# instruction-register.net
KiCad netlist of a schematic drawn in EAGLE
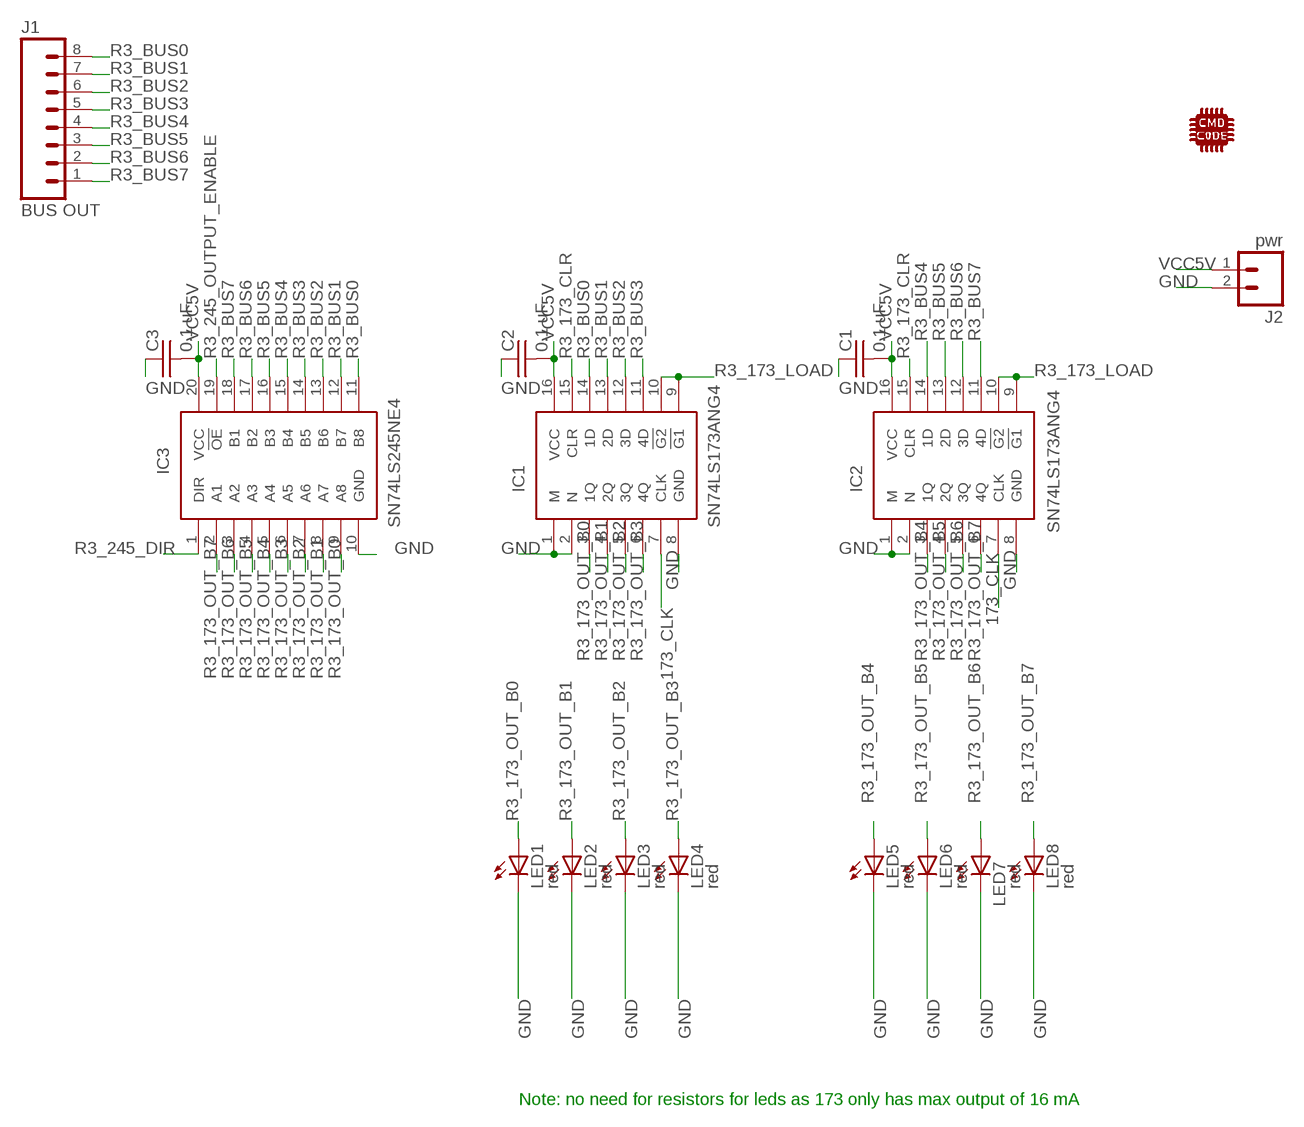
[diagram p0: schematic, sheet 1]
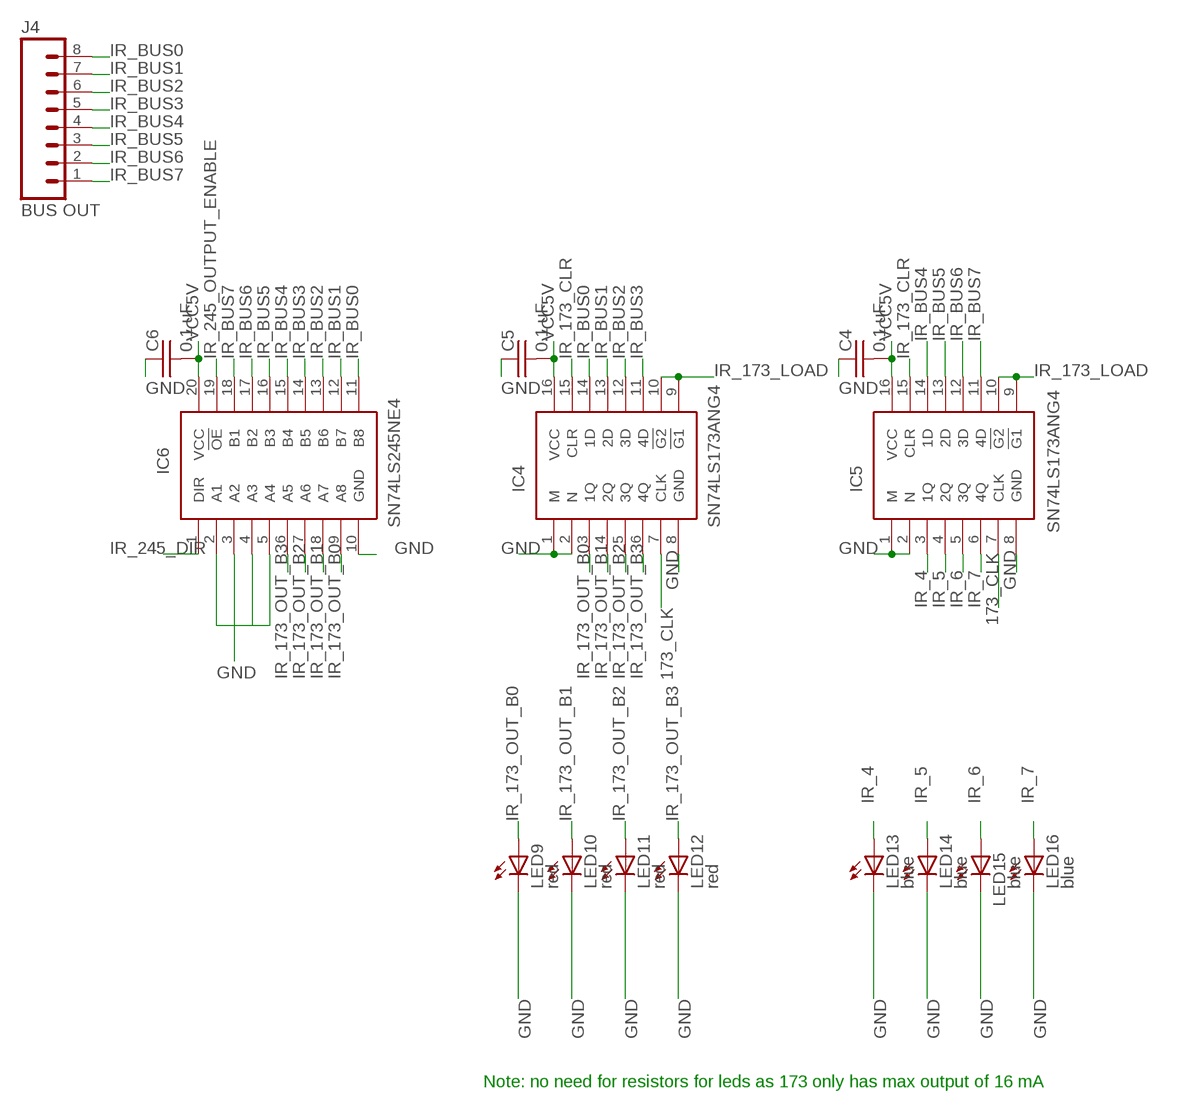
[diagram p1: schematic, sheet 2]
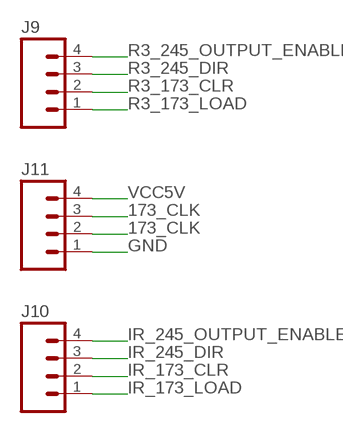
[diagram p2: schematic, sheet 3]

(export (version "E")
  (design (tool "Eeschema 10.0.6"))
  (components
    (comp (ref "C4")
      (value "0.1 uF")
      (footprint "eagle-import:C075-032X103")
      (libsource (lib "eagle-import") (part "C-US075-032X103"))
    )
    (comp (ref "C5")
      (value "0.1 uF")
      (footprint "eagle-import:C075-032X103")
      (libsource (lib "eagle-import") (part "C-US075-032X103"))
    )
    (comp (ref "C6")
      (value "0.1 uF")
      (footprint "eagle-import:C075-032X103")
      (libsource (lib "eagle-import") (part "C-US075-032X103"))
    )
    (comp (ref "IC4")
      (value "SN74LS173ANG4")
      (footprint "eagle-import:DIP794W53P254L1930H508Q16N")
      (libsource (lib "eagle-import") (part "SN74LS173ANG4"))
    )
    (comp (ref "IC5")
      (value "SN74LS173ANG4")
      (footprint "eagle-import:DIP794W53P254L1930H508Q16N")
      (libsource (lib "eagle-import") (part "SN74LS173ANG4"))
    )
    (comp (ref "IC6")
      (value "SN74LS245NE4")
      (footprint "eagle-import:DIP794W53P254L2540H508Q20N")
      (fields (field (name "MOUSER_PART_NUMBER") "595-SN74LS245NE4"))
      (libsource (lib "eagle-import") (part "SN74LS245NE4"))
    )
    (comp (ref "J4")
      (value "BUS OUT")
      (footprint "eagle-import:1X08_ROUND")
      (libsource (lib "eagle-import") (part "M08"))
    )
    (comp (ref "LED9")
      (value "red")
      (footprint "eagle-import:LED3MM")
      (libsource (lib "eagle-import") (part "LED3MM"))
    )
    (comp (ref "LED10")
      (value "red")
      (footprint "eagle-import:LED3MM")
      (libsource (lib "eagle-import") (part "LED3MM"))
    )
    (comp (ref "LED11")
      (value "red")
      (footprint "eagle-import:LED3MM")
      (libsource (lib "eagle-import") (part "LED3MM"))
    )
    (comp (ref "LED12")
      (value "red")
      (footprint "eagle-import:LED3MM")
      (libsource (lib "eagle-import") (part "LED3MM"))
    )
    (comp (ref "LED13")
      (value "blue")
      (footprint "eagle-import:LED3MM")
      (libsource (lib "eagle-import") (part "LED3MM"))
    )
    (comp (ref "LED14")
      (value "blue")
      (footprint "eagle-import:LED3MM")
      (libsource (lib "eagle-import") (part "LED3MM"))
    )
    (comp (ref "LED15")
      (value "blue")
      (footprint "eagle-import:LED3MM")
      (libsource (lib "eagle-import") (part "LED3MM"))
    )
    (comp (ref "LED16")
      (value "blue")
      (footprint "eagle-import:LED3MM")
      (libsource (lib "eagle-import") (part "LED3MM"))
    )
    (comp (ref "C1")
      (value "0.1 uF")
      (footprint "eagle-import:C075-032X103")
      (libsource (lib "eagle-import") (part "C-US075-032X103"))
    )
    (comp (ref "C2")
      (value "0.1 uF")
      (footprint "eagle-import:C075-032X103")
      (libsource (lib "eagle-import") (part "C-US075-032X103"))
    )
    (comp (ref "C3")
      (value "0.1 uF")
      (footprint "eagle-import:C075-032X103")
      (libsource (lib "eagle-import") (part "C-US075-032X103"))
    )
    (comp (ref "IC1")
      (value "SN74LS173ANG4")
      (footprint "eagle-import:DIP794W53P254L1930H508Q16N")
      (libsource (lib "eagle-import") (part "SN74LS173ANG4"))
    )
    (comp (ref "IC2")
      (value "SN74LS173ANG4")
      (footprint "eagle-import:DIP794W53P254L1930H508Q16N")
      (libsource (lib "eagle-import") (part "SN74LS173ANG4"))
    )
    (comp (ref "IC3")
      (value "SN74LS245NE4")
      (footprint "eagle-import:DIP794W53P254L2540H508Q20N")
      (fields (field (name "MOUSER_PART_NUMBER") "595-SN74LS245NE4"))
      (libsource (lib "eagle-import") (part "SN74LS245NE4"))
    )
    (comp (ref "J1")
      (value "BUS OUT")
      (footprint "eagle-import:1X08_ROUND")
      (libsource (lib "eagle-import") (part "M08"))
    )
    (comp (ref "J2")
      (value "pwr")
      (footprint "eagle-import:1X02")
      (libsource (lib "eagle-import") (part "M02PTH"))
    )
    (comp (ref "LED1")
      (value "red")
      (footprint "eagle-import:LED3MM")
      (libsource (lib "eagle-import") (part "LED3MM"))
    )
    (comp (ref "LED2")
      (value "red")
      (footprint "eagle-import:LED3MM")
      (libsource (lib "eagle-import") (part "LED3MM"))
    )
    (comp (ref "LED3")
      (value "red")
      (footprint "eagle-import:LED3MM")
      (libsource (lib "eagle-import") (part "LED3MM"))
    )
    (comp (ref "LED4")
      (value "red")
      (footprint "eagle-import:LED3MM")
      (libsource (lib "eagle-import") (part "LED3MM"))
    )
    (comp (ref "LED5")
      (value "red")
      (footprint "eagle-import:LED3MM")
      (libsource (lib "eagle-import") (part "LED3MM"))
    )
    (comp (ref "LED6")
      (value "red")
      (footprint "eagle-import:LED3MM")
      (libsource (lib "eagle-import") (part "LED3MM"))
    )
    (comp (ref "LED7")
      (value "red")
      (footprint "eagle-import:LED3MM")
      (libsource (lib "eagle-import") (part "LED3MM"))
    )
    (comp (ref "LED8")
      (value "red")
      (footprint "eagle-import:LED3MM")
      (libsource (lib "eagle-import") (part "LED3MM"))
    )
    (comp (ref "U$1")
      (value "CMD_C0DE_LOGOCMD_CODE_LOGO_TOP_COPPER")
      (footprint "eagle-import:CMD_C0DE_LOGO_TOP_COPPER")
      (libsource (lib "eagle-import") (part "CMD_C0DE_LOGOCMD_CODE_LOGO_TOP_COPPER"))
    )
    (comp (ref "J9")
      (value "M04PTH")
      (footprint "eagle-import:1X04")
      (libsource (lib "eagle-import") (part "M04PTH"))
    )
    (comp (ref "J10")
      (value "M04PTH")
      (footprint "eagle-import:1X04")
      (libsource (lib "eagle-import") (part "M04PTH"))
    )
    (comp (ref "J11")
      (value "M04PTH")
      (footprint "eagle-import:1X04")
      (libsource (lib "eagle-import") (part "M04PTH"))
    )
  )
  (nets
    (net (code "1") (name "173_CLK") (class "Default")
      (node (ref "IC1") (pin "7") (pinfunction "CLK_7") (pintype "bidirectional"))
      (node (ref "IC2") (pin "7") (pinfunction "CLK_7") (pintype "bidirectional"))
      (node (ref "IC4") (pin "7") (pinfunction "CLK_7") (pintype "bidirectional"))
      (node (ref "IC5") (pin "7") (pinfunction "CLK_7") (pintype "bidirectional"))
      (node (ref "J11") (pin "2") (pinfunction "2_2") (pintype "passive"))
      (node (ref "J11") (pin "3") (pinfunction "3_3") (pintype "passive"))
    )
    (net (code "2") (name "GND") (class "Default")
      (node (ref "C1") (pin "1") (pinfunction "1_1") (pintype "passive"))
      (node (ref "C2") (pin "1") (pinfunction "1_1") (pintype "passive"))
      (node (ref "C3") (pin "1") (pinfunction "1_1") (pintype "passive"))
      (node (ref "C4") (pin "1") (pinfunction "1_1") (pintype "passive"))
      (node (ref "C5") (pin "1") (pinfunction "1_1") (pintype "passive"))
      (node (ref "C6") (pin "1") (pinfunction "1_1") (pintype "passive"))
      (node (ref "IC1") (pin "1") (pinfunction "M_1") (pintype "bidirectional"))
      (node (ref "IC1") (pin "2") (pinfunction "N_2") (pintype "bidirectional"))
      (node (ref "IC1") (pin "8") (pinfunction "GND_8") (pintype "bidirectional"))
      (node (ref "IC2") (pin "1") (pinfunction "M_1") (pintype "bidirectional"))
      (node (ref "IC2") (pin "2") (pinfunction "N_2") (pintype "bidirectional"))
      (node (ref "IC2") (pin "8") (pinfunction "GND_8") (pintype "bidirectional"))
      (node (ref "IC3") (pin "10") (pinfunction "GND_10") (pintype "bidirectional"))
      (node (ref "IC4") (pin "1") (pinfunction "M_1") (pintype "bidirectional"))
      (node (ref "IC4") (pin "2") (pinfunction "N_2") (pintype "bidirectional"))
      (node (ref "IC4") (pin "8") (pinfunction "GND_8") (pintype "bidirectional"))
      (node (ref "IC5") (pin "1") (pinfunction "M_1") (pintype "bidirectional"))
      (node (ref "IC5") (pin "2") (pinfunction "N_2") (pintype "bidirectional"))
      (node (ref "IC5") (pin "8") (pinfunction "GND_8") (pintype "bidirectional"))
      (node (ref "IC6") (pin "10") (pinfunction "GND_10") (pintype "bidirectional"))
      (node (ref "IC6") (pin "2") (pinfunction "A1_2") (pintype "bidirectional"))
      (node (ref "IC6") (pin "3") (pinfunction "A2_3") (pintype "bidirectional"))
      (node (ref "IC6") (pin "4") (pinfunction "A3_4") (pintype "bidirectional"))
      (node (ref "IC6") (pin "5") (pinfunction "A4_5") (pintype "bidirectional"))
      (node (ref "J11") (pin "1") (pinfunction "1_1") (pintype "passive"))
      (node (ref "J2") (pin "2") (pinfunction "2_2") (pintype "passive"))
      (node (ref "LED1") (pin "K") (pinfunction "C_K") (pintype "output"))
      (node (ref "LED10") (pin "K") (pinfunction "C_K") (pintype "output"))
      (node (ref "LED11") (pin "K") (pinfunction "C_K") (pintype "output"))
      (node (ref "LED12") (pin "K") (pinfunction "C_K") (pintype "output"))
      (node (ref "LED13") (pin "K") (pinfunction "C_K") (pintype "output"))
      (node (ref "LED14") (pin "K") (pinfunction "C_K") (pintype "output"))
      (node (ref "LED15") (pin "K") (pinfunction "C_K") (pintype "output"))
      (node (ref "LED16") (pin "K") (pinfunction "C_K") (pintype "output"))
      (node (ref "LED2") (pin "K") (pinfunction "C_K") (pintype "output"))
      (node (ref "LED3") (pin "K") (pinfunction "C_K") (pintype "output"))
      (node (ref "LED4") (pin "K") (pinfunction "C_K") (pintype "output"))
      (node (ref "LED5") (pin "K") (pinfunction "C_K") (pintype "output"))
      (node (ref "LED6") (pin "K") (pinfunction "C_K") (pintype "output"))
      (node (ref "LED7") (pin "K") (pinfunction "C_K") (pintype "output"))
      (node (ref "LED8") (pin "K") (pinfunction "C_K") (pintype "output"))
      (node (ref "LED9") (pin "K") (pinfunction "C_K") (pintype "output"))
    )
    (net (code "3") (name "IR_4") (class "Default")
      (node (ref "IC5") (pin "3") (pinfunction "1Q_3") (pintype "bidirectional"))
      (node (ref "LED13") (pin "A") (pinfunction "A_A") (pintype "input"))
    )
    (net (code "4") (name "IR_5") (class "Default")
      (node (ref "IC5") (pin "4") (pinfunction "2Q_4") (pintype "bidirectional"))
      (node (ref "LED14") (pin "A") (pinfunction "A_A") (pintype "input"))
    )
    (net (code "5") (name "IR_6") (class "Default")
      (node (ref "IC5") (pin "5") (pinfunction "3Q_5") (pintype "bidirectional"))
      (node (ref "LED15") (pin "A") (pinfunction "A_A") (pintype "input"))
    )
    (net (code "6") (name "IR_7") (class "Default")
      (node (ref "IC5") (pin "6") (pinfunction "4Q_6") (pintype "bidirectional"))
      (node (ref "LED16") (pin "A") (pinfunction "A_A") (pintype "input"))
    )
    (net (code "7") (name "IR_173_CLR") (class "Default")
      (node (ref "IC4") (pin "15") (pinfunction "CLR_15") (pintype "bidirectional"))
      (node (ref "IC5") (pin "15") (pinfunction "CLR_15") (pintype "bidirectional"))
      (node (ref "J10") (pin "2") (pinfunction "2_2") (pintype "passive"))
    )
    (net (code "8") (name "IR_173_LOAD") (class "Default")
      (node (ref "IC4") (pin "10") (pinfunction "~{G2}_10") (pintype "bidirectional"))
      (node (ref "IC4") (pin "9") (pinfunction "~{G1}_9") (pintype "bidirectional"))
      (node (ref "IC5") (pin "10") (pinfunction "~{G2}_10") (pintype "bidirectional"))
      (node (ref "IC5") (pin "9") (pinfunction "~{G1}_9") (pintype "bidirectional"))
      (node (ref "J10") (pin "1") (pinfunction "1_1") (pintype "passive"))
    )
    (net (code "9") (name "IR_173_OUT_B0") (class "Default")
      (node (ref "IC4") (pin "3") (pinfunction "1Q_3") (pintype "bidirectional"))
      (node (ref "IC6") (pin "9") (pinfunction "A8_9") (pintype "bidirectional"))
      (node (ref "LED9") (pin "A") (pinfunction "A_A") (pintype "input"))
    )
    (net (code "10") (name "IR_173_OUT_B1") (class "Default")
      (node (ref "IC4") (pin "4") (pinfunction "2Q_4") (pintype "bidirectional"))
      (node (ref "IC6") (pin "8") (pinfunction "A7_8") (pintype "bidirectional"))
      (node (ref "LED10") (pin "A") (pinfunction "A_A") (pintype "input"))
    )
    (net (code "11") (name "IR_173_OUT_B2") (class "Default")
      (node (ref "IC4") (pin "5") (pinfunction "3Q_5") (pintype "bidirectional"))
      (node (ref "IC6") (pin "7") (pinfunction "A6_7") (pintype "bidirectional"))
      (node (ref "LED11") (pin "A") (pinfunction "A_A") (pintype "input"))
    )
    (net (code "12") (name "IR_173_OUT_B3") (class "Default")
      (node (ref "IC4") (pin "6") (pinfunction "4Q_6") (pintype "bidirectional"))
      (node (ref "IC6") (pin "6") (pinfunction "A5_6") (pintype "bidirectional"))
      (node (ref "LED12") (pin "A") (pinfunction "A_A") (pintype "input"))
    )
    (net (code "13") (name "IR_245_DIR") (class "Default")
      (node (ref "IC6") (pin "1") (pinfunction "DIR_1") (pintype "bidirectional"))
      (node (ref "J10") (pin "3") (pinfunction "3_3") (pintype "passive"))
    )
    (net (code "14") (name "IR_245_OUTPUT_ENABLE") (class "Default")
      (node (ref "IC6") (pin "19") (pinfunction "~{OE}_19") (pintype "bidirectional"))
      (node (ref "J10") (pin "4") (pinfunction "4_4") (pintype "passive"))
    )
    (net (code "15") (name "IR_BUS0") (class "Default")
      (node (ref "IC4") (pin "14") (pinfunction "1D_14") (pintype "bidirectional"))
      (node (ref "IC6") (pin "11") (pinfunction "B8_11") (pintype "bidirectional"))
      (node (ref "J4") (pin "8") (pinfunction "8_8") (pintype "passive"))
    )
    (net (code "16") (name "IR_BUS1") (class "Default")
      (node (ref "IC4") (pin "13") (pinfunction "2D_13") (pintype "bidirectional"))
      (node (ref "IC6") (pin "12") (pinfunction "B7_12") (pintype "bidirectional"))
      (node (ref "J4") (pin "7") (pinfunction "7_7") (pintype "passive"))
    )
    (net (code "17") (name "IR_BUS2") (class "Default")
      (node (ref "IC4") (pin "12") (pinfunction "3D_12") (pintype "bidirectional"))
      (node (ref "IC6") (pin "13") (pinfunction "B6_13") (pintype "bidirectional"))
      (node (ref "J4") (pin "6") (pinfunction "6_6") (pintype "passive"))
    )
    (net (code "18") (name "IR_BUS3") (class "Default")
      (node (ref "IC4") (pin "11") (pinfunction "4D_11") (pintype "bidirectional"))
      (node (ref "IC6") (pin "14") (pinfunction "B5_14") (pintype "bidirectional"))
      (node (ref "J4") (pin "5") (pinfunction "5_5") (pintype "passive"))
    )
    (net (code "19") (name "IR_BUS4") (class "Default")
      (node (ref "IC5") (pin "14") (pinfunction "1D_14") (pintype "bidirectional"))
      (node (ref "IC6") (pin "15") (pinfunction "B4_15") (pintype "bidirectional"))
      (node (ref "J4") (pin "4") (pinfunction "4_4") (pintype "passive"))
    )
    (net (code "20") (name "IR_BUS5") (class "Default")
      (node (ref "IC5") (pin "13") (pinfunction "2D_13") (pintype "bidirectional"))
      (node (ref "IC6") (pin "16") (pinfunction "B3_16") (pintype "bidirectional"))
      (node (ref "J4") (pin "3") (pinfunction "3_3") (pintype "passive"))
    )
    (net (code "21") (name "IR_BUS6") (class "Default")
      (node (ref "IC5") (pin "12") (pinfunction "3D_12") (pintype "bidirectional"))
      (node (ref "IC6") (pin "17") (pinfunction "B2_17") (pintype "bidirectional"))
      (node (ref "J4") (pin "2") (pinfunction "2_2") (pintype "passive"))
    )
    (net (code "22") (name "IR_BUS7") (class "Default")
      (node (ref "IC5") (pin "11") (pinfunction "4D_11") (pintype "bidirectional"))
      (node (ref "IC6") (pin "18") (pinfunction "B1_18") (pintype "bidirectional"))
      (node (ref "J4") (pin "1") (pinfunction "1_1") (pintype "passive"))
    )
    (net (code "23") (name "R3_173_CLR") (class "Default")
      (node (ref "IC1") (pin "15") (pinfunction "CLR_15") (pintype "bidirectional"))
      (node (ref "IC2") (pin "15") (pinfunction "CLR_15") (pintype "bidirectional"))
      (node (ref "J9") (pin "2") (pinfunction "2_2") (pintype "passive"))
    )
    (net (code "24") (name "R3_173_LOAD") (class "Default")
      (node (ref "IC1") (pin "10") (pinfunction "~{G2}_10") (pintype "bidirectional"))
      (node (ref "IC1") (pin "9") (pinfunction "~{G1}_9") (pintype "bidirectional"))
      (node (ref "IC2") (pin "10") (pinfunction "~{G2}_10") (pintype "bidirectional"))
      (node (ref "IC2") (pin "9") (pinfunction "~{G1}_9") (pintype "bidirectional"))
      (node (ref "J9") (pin "1") (pinfunction "1_1") (pintype "passive"))
    )
    (net (code "25") (name "R3_173_OUT_B0") (class "Default")
      (node (ref "IC1") (pin "3") (pinfunction "1Q_3") (pintype "bidirectional"))
      (node (ref "IC3") (pin "9") (pinfunction "A8_9") (pintype "bidirectional"))
      (node (ref "LED1") (pin "A") (pinfunction "A_A") (pintype "input"))
    )
    (net (code "26") (name "R3_173_OUT_B1") (class "Default")
      (node (ref "IC1") (pin "4") (pinfunction "2Q_4") (pintype "bidirectional"))
      (node (ref "IC3") (pin "8") (pinfunction "A7_8") (pintype "bidirectional"))
      (node (ref "LED2") (pin "A") (pinfunction "A_A") (pintype "input"))
    )
    (net (code "27") (name "R3_173_OUT_B2") (class "Default")
      (node (ref "IC1") (pin "5") (pinfunction "3Q_5") (pintype "bidirectional"))
      (node (ref "IC3") (pin "7") (pinfunction "A6_7") (pintype "bidirectional"))
      (node (ref "LED3") (pin "A") (pinfunction "A_A") (pintype "input"))
    )
    (net (code "28") (name "R3_173_OUT_B3") (class "Default")
      (node (ref "IC1") (pin "6") (pinfunction "4Q_6") (pintype "bidirectional"))
      (node (ref "IC3") (pin "6") (pinfunction "A5_6") (pintype "bidirectional"))
      (node (ref "LED4") (pin "A") (pinfunction "A_A") (pintype "input"))
    )
    (net (code "29") (name "R3_173_OUT_B4") (class "Default")
      (node (ref "IC2") (pin "3") (pinfunction "1Q_3") (pintype "bidirectional"))
      (node (ref "IC3") (pin "5") (pinfunction "A4_5") (pintype "bidirectional"))
      (node (ref "LED5") (pin "A") (pinfunction "A_A") (pintype "input"))
    )
    (net (code "30") (name "R3_173_OUT_B5") (class "Default")
      (node (ref "IC2") (pin "4") (pinfunction "2Q_4") (pintype "bidirectional"))
      (node (ref "IC3") (pin "4") (pinfunction "A3_4") (pintype "bidirectional"))
      (node (ref "LED6") (pin "A") (pinfunction "A_A") (pintype "input"))
    )
    (net (code "31") (name "R3_173_OUT_B6") (class "Default")
      (node (ref "IC2") (pin "5") (pinfunction "3Q_5") (pintype "bidirectional"))
      (node (ref "IC3") (pin "3") (pinfunction "A2_3") (pintype "bidirectional"))
      (node (ref "LED7") (pin "A") (pinfunction "A_A") (pintype "input"))
    )
    (net (code "32") (name "R3_173_OUT_B7") (class "Default")
      (node (ref "IC2") (pin "6") (pinfunction "4Q_6") (pintype "bidirectional"))
      (node (ref "IC3") (pin "2") (pinfunction "A1_2") (pintype "bidirectional"))
      (node (ref "LED8") (pin "A") (pinfunction "A_A") (pintype "input"))
    )
    (net (code "33") (name "R3_245_DIR") (class "Default")
      (node (ref "IC3") (pin "1") (pinfunction "DIR_1") (pintype "bidirectional"))
      (node (ref "J9") (pin "3") (pinfunction "3_3") (pintype "passive"))
    )
    (net (code "34") (name "R3_245_OUTPUT_ENABLE") (class "Default")
      (node (ref "IC3") (pin "19") (pinfunction "~{OE}_19") (pintype "bidirectional"))
      (node (ref "J9") (pin "4") (pinfunction "4_4") (pintype "passive"))
    )
    (net (code "35") (name "R3_BUS0") (class "Default")
      (node (ref "IC1") (pin "14") (pinfunction "1D_14") (pintype "bidirectional"))
      (node (ref "IC3") (pin "11") (pinfunction "B8_11") (pintype "bidirectional"))
      (node (ref "J1") (pin "8") (pinfunction "8_8") (pintype "passive"))
    )
    (net (code "36") (name "R3_BUS1") (class "Default")
      (node (ref "IC1") (pin "13") (pinfunction "2D_13") (pintype "bidirectional"))
      (node (ref "IC3") (pin "12") (pinfunction "B7_12") (pintype "bidirectional"))
      (node (ref "J1") (pin "7") (pinfunction "7_7") (pintype "passive"))
    )
    (net (code "37") (name "R3_BUS2") (class "Default")
      (node (ref "IC1") (pin "12") (pinfunction "3D_12") (pintype "bidirectional"))
      (node (ref "IC3") (pin "13") (pinfunction "B6_13") (pintype "bidirectional"))
      (node (ref "J1") (pin "6") (pinfunction "6_6") (pintype "passive"))
    )
    (net (code "38") (name "R3_BUS3") (class "Default")
      (node (ref "IC1") (pin "11") (pinfunction "4D_11") (pintype "bidirectional"))
      (node (ref "IC3") (pin "14") (pinfunction "B5_14") (pintype "bidirectional"))
      (node (ref "J1") (pin "5") (pinfunction "5_5") (pintype "passive"))
    )
    (net (code "39") (name "R3_BUS4") (class "Default")
      (node (ref "IC2") (pin "14") (pinfunction "1D_14") (pintype "bidirectional"))
      (node (ref "IC3") (pin "15") (pinfunction "B4_15") (pintype "bidirectional"))
      (node (ref "J1") (pin "4") (pinfunction "4_4") (pintype "passive"))
    )
    (net (code "40") (name "R3_BUS5") (class "Default")
      (node (ref "IC2") (pin "13") (pinfunction "2D_13") (pintype "bidirectional"))
      (node (ref "IC3") (pin "16") (pinfunction "B3_16") (pintype "bidirectional"))
      (node (ref "J1") (pin "3") (pinfunction "3_3") (pintype "passive"))
    )
    (net (code "41") (name "R3_BUS6") (class "Default")
      (node (ref "IC2") (pin "12") (pinfunction "3D_12") (pintype "bidirectional"))
      (node (ref "IC3") (pin "17") (pinfunction "B2_17") (pintype "bidirectional"))
      (node (ref "J1") (pin "2") (pinfunction "2_2") (pintype "passive"))
    )
    (net (code "42") (name "R3_BUS7") (class "Default")
      (node (ref "IC2") (pin "11") (pinfunction "4D_11") (pintype "bidirectional"))
      (node (ref "IC3") (pin "18") (pinfunction "B1_18") (pintype "bidirectional"))
      (node (ref "J1") (pin "1") (pinfunction "1_1") (pintype "passive"))
    )
    (net (code "43") (name "VCC5V") (class "Default")
      (node (ref "C1") (pin "2") (pinfunction "2_2") (pintype "passive"))
      (node (ref "C2") (pin "2") (pinfunction "2_2") (pintype "passive"))
      (node (ref "C3") (pin "2") (pinfunction "2_2") (pintype "passive"))
      (node (ref "C4") (pin "2") (pinfunction "2_2") (pintype "passive"))
      (node (ref "C5") (pin "2") (pinfunction "2_2") (pintype "passive"))
      (node (ref "C6") (pin "2") (pinfunction "2_2") (pintype "passive"))
      (node (ref "IC1") (pin "16") (pinfunction "VCC_16") (pintype "bidirectional"))
      (node (ref "IC2") (pin "16") (pinfunction "VCC_16") (pintype "bidirectional"))
      (node (ref "IC3") (pin "20") (pinfunction "VCC_20") (pintype "bidirectional"))
      (node (ref "IC4") (pin "16") (pinfunction "VCC_16") (pintype "bidirectional"))
      (node (ref "IC5") (pin "16") (pinfunction "VCC_16") (pintype "bidirectional"))
      (node (ref "IC6") (pin "20") (pinfunction "VCC_20") (pintype "bidirectional"))
      (node (ref "J11") (pin "4") (pinfunction "4_4") (pintype "passive"))
      (node (ref "J2") (pin "1") (pinfunction "1_1") (pintype "passive"))
    )
  )
)
